# 17_FPGA_B12_B13_B14_B15.net
KiCad netlist of a schematic drawn in Altium Designer
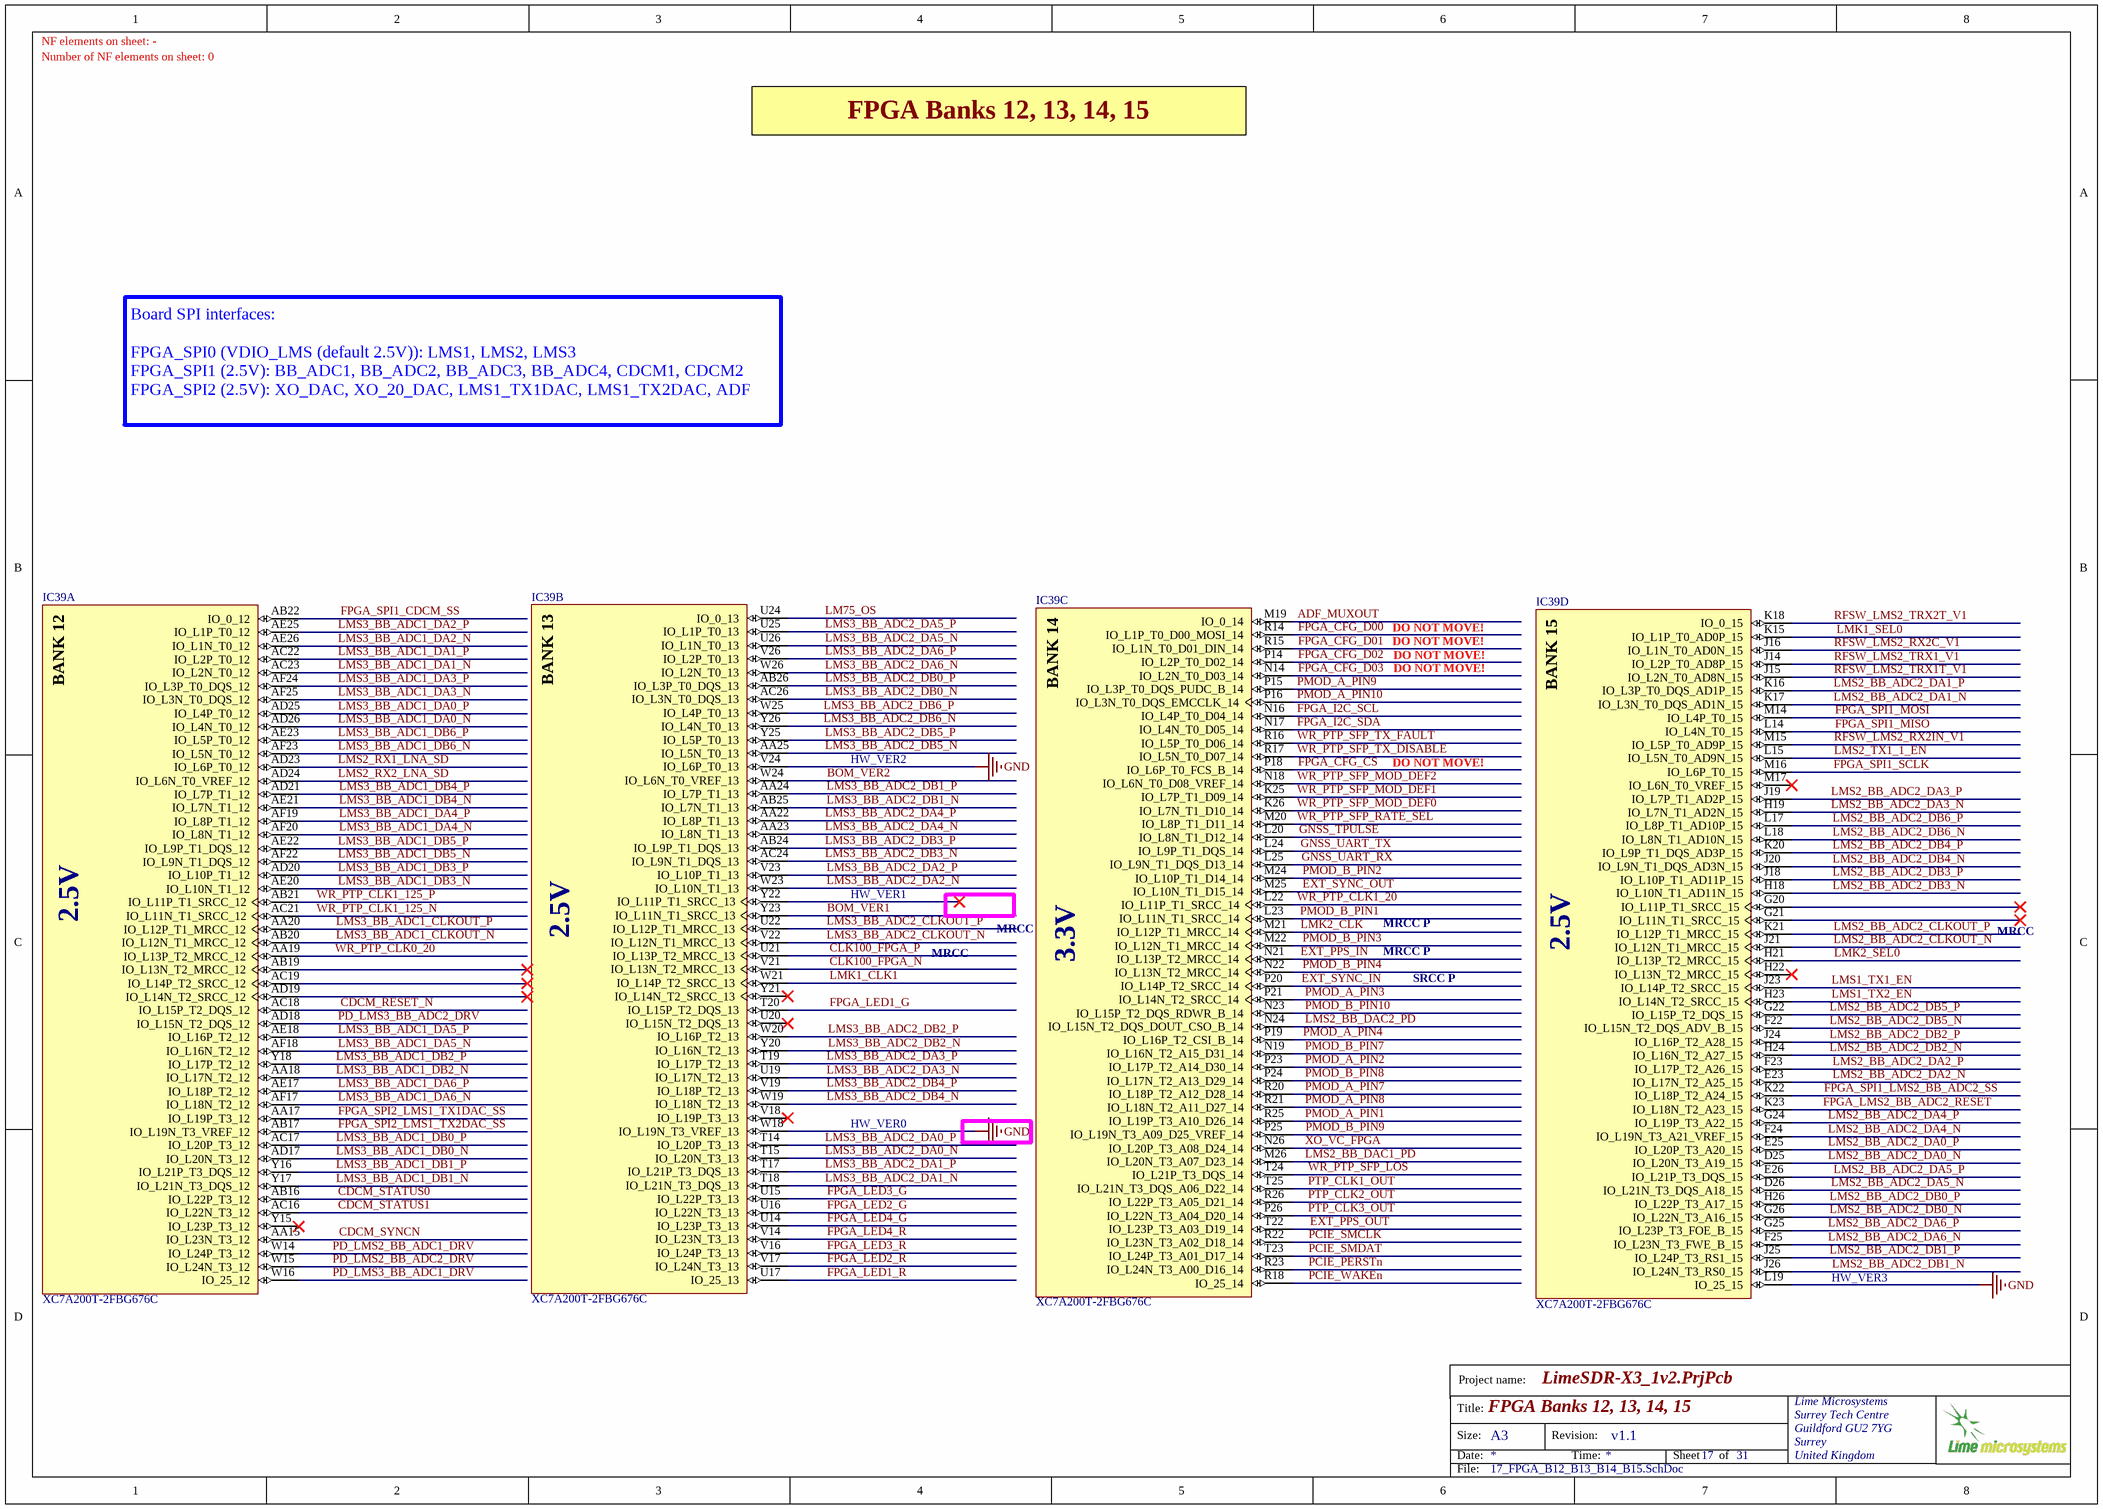
[diagram p0: 17_FPGA_B12_B13_B14_B15.SchDoc]

(export (version "E")
  (design (tool "Eeschema 10.0.6"))
  (components
    (comp (ref "IC39")
      (value "XC7A200T-2FBG676C")
      (footprint "XC7A200T-2FBG676C_FBG676")
      (description "Artix-7 FPGA, 400 User I/Os, 8 GTP, 676-Ball BGA, Speed Grade 2, Commercial Grade, Pb-Free")
      (fields (field (name "MANUFACTURER") "Xilinx"))
      (libsource (lib "LimeMicroAltiumLib_schLib_r02") (part "XC7A200T-2FBG676C"))
    )
  )
  (nets
    (net (code "1") (name "/ADF_MUXOUT") (class "Default")
      (node (ref "IC39") (pin "M19") (pinfunction "IO_0_14_M19") (pintype "bidirectional"))
    )
    (net (code "2") (name "/BOM_VER1") (class "Default")
      (node (ref "IC39") (pin "Y23") (pinfunction "IO_L11N_T1_SRCC_13_Y23") (pintype "bidirectional"))
    )
    (net (code "3") (name "/BOM_VER2") (class "Default")
      (node (ref "IC39") (pin "W24") (pinfunction "IO_L6N_T0_VREF_13_W24") (pintype "bidirectional"))
    )
    (net (code "4") (name "/CDCM_RESET_N") (class "Default")
      (node (ref "IC39") (pin "AC18") (pinfunction "IO_L15P_T2_DQS_12_AC18") (pintype "bidirectional"))
    )
    (net (code "5") (name "/CDCM_STATUS0") (class "Default")
      (node (ref "IC39") (pin "AB16") (pinfunction "IO_L22P_T3_12_AB16") (pintype "bidirectional"))
    )
    (net (code "6") (name "/CDCM_STATUS1") (class "Default")
      (node (ref "IC39") (pin "AC16") (pinfunction "IO_L22N_T3_12_AC16") (pintype "bidirectional"))
    )
    (net (code "7") (name "/CDCM_SYNCN") (class "Default")
      (node (ref "IC39") (pin "AA15") (pinfunction "IO_L23N_T3_12_AA15") (pintype "bidirectional"))
    )
    (net (code "8") (name "/CLK100_FPGA_N") (class "Default")
      (node (ref "IC39") (pin "V21") (pinfunction "IO_L13N_T2_MRCC_13_V21") (pintype "bidirectional"))
    )
    (net (code "9") (name "/CLK100_FPGA_P") (class "Default")
      (node (ref "IC39") (pin "U21") (pinfunction "IO_L13P_T2_MRCC_13_U21") (pintype "bidirectional"))
    )
    (net (code "10") (name "/EXT_PPS_IN") (class "Default")
      (node (ref "IC39") (pin "N21") (pinfunction "IO_L13P_T2_MRCC_14_N21") (pintype "bidirectional"))
    )
    (net (code "11") (name "/EXT_PPS_OUT") (class "Default")
      (node (ref "IC39") (pin "T22") (pinfunction "IO_L23P_T3_A03_D19_14_T22") (pintype "bidirectional"))
    )
    (net (code "12") (name "/EXT_SYNC_IN") (class "Default")
      (node (ref "IC39") (pin "P20") (pinfunction "IO_L14P_T2_SRCC_14_P20") (pintype "bidirectional"))
    )
    (net (code "13") (name "/EXT_SYNC_OUT") (class "Default")
      (node (ref "IC39") (pin "M25") (pinfunction "IO_L10N_T1_D15_14_M25") (pintype "bidirectional"))
    )
    (net (code "14") (name "/FPGA_CFG_CS") (class "Default")
      (node (ref "IC39") (pin "P18") (pinfunction "IO_L6P_T0_FCS_B_14_P18") (pintype "bidirectional"))
    )
    (net (code "15") (name "/FPGA_CFG_D00") (class "Default")
      (node (ref "IC39") (pin "R14") (pinfunction "IO_L1P_T0_D00_MOSI_14_R14") (pintype "bidirectional"))
    )
    (net (code "16") (name "/FPGA_CFG_D01") (class "Default")
      (node (ref "IC39") (pin "R15") (pinfunction "IO_L1N_T0_D01_DIN_14_R15") (pintype "bidirectional"))
    )
    (net (code "17") (name "/FPGA_CFG_D02") (class "Default")
      (node (ref "IC39") (pin "P14") (pinfunction "IO_L2P_T0_D02_14_P14") (pintype "bidirectional"))
    )
    (net (code "18") (name "/FPGA_CFG_D03") (class "Default")
      (node (ref "IC39") (pin "N14") (pinfunction "IO_L2N_T0_D03_14_N14") (pintype "bidirectional"))
    )
    (net (code "19") (name "/FPGA_I2C_SCL") (class "Default")
      (node (ref "IC39") (pin "N16") (pinfunction "IO_L4P_T0_D04_14_N16") (pintype "bidirectional"))
    )
    (net (code "20") (name "/FPGA_I2C_SDA") (class "Default")
      (node (ref "IC39") (pin "N17") (pinfunction "IO_L4N_T0_D05_14_N17") (pintype "bidirectional"))
    )
    (net (code "21") (name "/FPGA_LED1_G") (class "Default")
      (node (ref "IC39") (pin "T20") (pinfunction "IO_L15P_T2_DQS_13_T20") (pintype "bidirectional"))
    )
    (net (code "22") (name "/FPGA_LED1_R") (class "Default")
      (node (ref "IC39") (pin "U17") (pinfunction "IO_25_13_U17") (pintype "bidirectional"))
    )
    (net (code "23") (name "/FPGA_LED2_G") (class "Default")
      (node (ref "IC39") (pin "U16") (pinfunction "IO_L22N_T3_13_U16") (pintype "bidirectional"))
    )
    (net (code "24") (name "/FPGA_LED2_R") (class "Default")
      (node (ref "IC39") (pin "V17") (pinfunction "IO_L24N_T3_13_V17") (pintype "bidirectional"))
    )
    (net (code "25") (name "/FPGA_LED3_G") (class "Default")
      (node (ref "IC39") (pin "U15") (pinfunction "IO_L22P_T3_13_U15") (pintype "bidirectional"))
    )
    (net (code "26") (name "/FPGA_LED3_R") (class "Default")
      (node (ref "IC39") (pin "V16") (pinfunction "IO_L24P_T3_13_V16") (pintype "bidirectional"))
    )
    (net (code "27") (name "/FPGA_LED4_G") (class "Default")
      (node (ref "IC39") (pin "U14") (pinfunction "IO_L23P_T3_13_U14") (pintype "bidirectional"))
    )
    (net (code "28") (name "/FPGA_LED4_R") (class "Default")
      (node (ref "IC39") (pin "V14") (pinfunction "IO_L23N_T3_13_V14") (pintype "bidirectional"))
    )
    (net (code "29") (name "/FPGA_LMS2_BB_ADC2_RESET") (class "Default")
      (node (ref "IC39") (pin "K23") (pinfunction "IO_L18N_T2_A23_15_K23") (pintype "bidirectional"))
    )
    (net (code "30") (name "/FPGA_SPI1_CDCM_SS") (class "Default")
      (node (ref "IC39") (pin "AB22") (pinfunction "IO_0_12_AB22") (pintype "bidirectional"))
    )
    (net (code "31") (name "/FPGA_SPI1_LMS2_BB_ADC2_SS") (class "Default")
      (node (ref "IC39") (pin "K22") (pinfunction "IO_L18P_T2_A24_15_K22") (pintype "bidirectional"))
    )
    (net (code "32") (name "/FPGA_SPI1_MISO") (class "Default")
      (node (ref "IC39") (pin "L14") (pinfunction "IO_L4N_T0_15_L14") (pintype "bidirectional"))
    )
    (net (code "33") (name "/FPGA_SPI1_MOSI") (class "Default")
      (node (ref "IC39") (pin "M14") (pinfunction "IO_L4P_T0_15_M14") (pintype "bidirectional"))
    )
    (net (code "34") (name "/FPGA_SPI1_SCLK") (class "Default")
      (node (ref "IC39") (pin "M16") (pinfunction "IO_L6P_T0_15_M16") (pintype "bidirectional"))
    )
    (net (code "35") (name "/FPGA_SPI2_LMS1_TX1DAC_SS") (class "Default")
      (node (ref "IC39") (pin "AA17") (pinfunction "IO_L19P_T3_12_AA17") (pintype "bidirectional"))
    )
    (net (code "36") (name "/FPGA_SPI2_LMS1_TX2DAC_SS") (class "Default")
      (node (ref "IC39") (pin "AB17") (pinfunction "IO_L19N_T3_VREF_12_AB17") (pintype "bidirectional"))
    )
    (net (code "37") (name "/GNSS_TPULSE") (class "Default")
      (node (ref "IC39") (pin "L20") (pinfunction "IO_L8N_T1_D12_14_L20") (pintype "bidirectional"))
    )
    (net (code "38") (name "/GNSS_UART_RX") (class "Default")
      (node (ref "IC39") (pin "L25") (pinfunction "IO_L9N_T1_DQS_D13_14_L25") (pintype "bidirectional"))
    )
    (net (code "39") (name "/GNSS_UART_TX") (class "Default")
      (node (ref "IC39") (pin "L24") (pinfunction "IO_L9P_T1_DQS_14_L24") (pintype "bidirectional"))
    )
    (net (code "40") (name "/LM75_OS") (class "Default")
      (node (ref "IC39") (pin "U24") (pinfunction "IO_0_13_U24") (pintype "bidirectional"))
    )
    (net (code "41") (name "/LMK1_CLK1") (class "Default")
      (node (ref "IC39") (pin "W21") (pinfunction "IO_L14P_T2_SRCC_13_W21") (pintype "bidirectional"))
    )
    (net (code "42") (name "/LMK1_SEL0") (class "Default")
      (node (ref "IC39") (pin "K15") (pinfunction "IO_L1P_T0_AD0P_15_K15") (pintype "bidirectional"))
    )
    (net (code "43") (name "/LMK2_CLK") (class "Default")
      (node (ref "IC39") (pin "M21") (pinfunction "IO_L12P_T1_MRCC_14_M21") (pintype "bidirectional"))
    )
    (net (code "44") (name "/LMK2_SEL0") (class "Default")
      (node (ref "IC39") (pin "H21") (pinfunction "IO_L13P_T2_MRCC_15_H21") (pintype "bidirectional"))
    )
    (net (code "45") (name "/LMS1_TX1_EN") (class "Default")
      (node (ref "IC39") (pin "J23") (pinfunction "IO_L14P_T2_SRCC_15_J23") (pintype "bidirectional"))
    )
    (net (code "46") (name "/LMS1_TX2_EN") (class "Default")
      (node (ref "IC39") (pin "H23") (pinfunction "IO_L14N_T2_SRCC_15_H23") (pintype "bidirectional"))
    )
    (net (code "47") (name "/LMS2_BB_ADC2_CLKOUT_N") (class "Default")
      (node (ref "IC39") (pin "J21") (pinfunction "IO_L12N_T1_MRCC_15_J21") (pintype "bidirectional"))
    )
    (net (code "48") (name "/LMS2_BB_ADC2_CLKOUT_P") (class "Default")
      (node (ref "IC39") (pin "K21") (pinfunction "IO_L12P_T1_MRCC_15_K21") (pintype "bidirectional"))
    )
    (net (code "49") (name "/LMS2_BB_ADC2_DA0_N") (class "Default")
      (node (ref "IC39") (pin "D25") (pinfunction "IO_L20N_T3_A19_15_D25") (pintype "bidirectional"))
    )
    (net (code "50") (name "/LMS2_BB_ADC2_DA0_P") (class "Default")
      (node (ref "IC39") (pin "E25") (pinfunction "IO_L20P_T3_A20_15_E25") (pintype "bidirectional"))
    )
    (net (code "51") (name "/LMS2_BB_ADC2_DA1_N") (class "Default")
      (node (ref "IC39") (pin "K17") (pinfunction "IO_L3N_T0_DQS_AD1N_15_K17") (pintype "bidirectional"))
    )
    (net (code "52") (name "/LMS2_BB_ADC2_DA1_P") (class "Default")
      (node (ref "IC39") (pin "K16") (pinfunction "IO_L3P_T0_DQS_AD1P_15_K16") (pintype "bidirectional"))
    )
    (net (code "53") (name "/LMS2_BB_ADC2_DA2_N") (class "Default")
      (node (ref "IC39") (pin "E23") (pinfunction "IO_L17N_T2_A25_15_E23") (pintype "bidirectional"))
    )
    (net (code "54") (name "/LMS2_BB_ADC2_DA2_P") (class "Default")
      (node (ref "IC39") (pin "F23") (pinfunction "IO_L17P_T2_A26_15_F23") (pintype "bidirectional"))
    )
    (net (code "55") (name "/LMS2_BB_ADC2_DA3_N") (class "Default")
      (node (ref "IC39") (pin "H19") (pinfunction "IO_L7N_T1_AD2N_15_H19") (pintype "bidirectional"))
    )
    (net (code "56") (name "/LMS2_BB_ADC2_DA3_P") (class "Default")
      (node (ref "IC39") (pin "J19") (pinfunction "IO_L7P_T1_AD2P_15_J19") (pintype "bidirectional"))
    )
    (net (code "57") (name "/LMS2_BB_ADC2_DA4_N") (class "Default")
      (node (ref "IC39") (pin "F24") (pinfunction "IO_L19N_T3_A21_VREF_15_F24") (pintype "bidirectional"))
    )
    (net (code "58") (name "/LMS2_BB_ADC2_DA4_P") (class "Default")
      (node (ref "IC39") (pin "G24") (pinfunction "IO_L19P_T3_A22_15_G24") (pintype "bidirectional"))
    )
    (net (code "59") (name "/LMS2_BB_ADC2_DA5_N") (class "Default")
      (node (ref "IC39") (pin "D26") (pinfunction "IO_L21N_T3_DQS_A18_15_D26") (pintype "bidirectional"))
    )
    (net (code "60") (name "/LMS2_BB_ADC2_DA5_P") (class "Default")
      (node (ref "IC39") (pin "E26") (pinfunction "IO_L21P_T3_DQS_15_E26") (pintype "bidirectional"))
    )
    (net (code "61") (name "/LMS2_BB_ADC2_DA6_N") (class "Default")
      (node (ref "IC39") (pin "F25") (pinfunction "IO_L23N_T3_FWE_B_15_F25") (pintype "bidirectional"))
    )
    (net (code "62") (name "/LMS2_BB_ADC2_DA6_P") (class "Default")
      (node (ref "IC39") (pin "G25") (pinfunction "IO_L23P_T3_FOE_B_15_G25") (pintype "bidirectional"))
    )
    (net (code "63") (name "/LMS2_BB_ADC2_DB0_N") (class "Default")
      (node (ref "IC39") (pin "G26") (pinfunction "IO_L22N_T3_A16_15_G26") (pintype "bidirectional"))
    )
    (net (code "64") (name "/LMS2_BB_ADC2_DB0_P") (class "Default")
      (node (ref "IC39") (pin "H26") (pinfunction "IO_L22P_T3_A17_15_H26") (pintype "bidirectional"))
    )
    (net (code "65") (name "/LMS2_BB_ADC2_DB1_N") (class "Default")
      (node (ref "IC39") (pin "J26") (pinfunction "IO_L24N_T3_RS0_15_J26") (pintype "bidirectional"))
    )
    (net (code "66") (name "/LMS2_BB_ADC2_DB1_P") (class "Default")
      (node (ref "IC39") (pin "J25") (pinfunction "IO_L24P_T3_RS1_15_J25") (pintype "bidirectional"))
    )
    (net (code "67") (name "/LMS2_BB_ADC2_DB2_N") (class "Default")
      (node (ref "IC39") (pin "H24") (pinfunction "IO_L16N_T2_A27_15_H24") (pintype "bidirectional"))
    )
    (net (code "68") (name "/LMS2_BB_ADC2_DB2_P") (class "Default")
      (node (ref "IC39") (pin "J24") (pinfunction "IO_L16P_T2_A28_15_J24") (pintype "bidirectional"))
    )
    (net (code "69") (name "/LMS2_BB_ADC2_DB3_N") (class "Default")
      (node (ref "IC39") (pin "H18") (pinfunction "IO_L10N_T1_AD11N_15_H18") (pintype "bidirectional"))
    )
    (net (code "70") (name "/LMS2_BB_ADC2_DB3_P") (class "Default")
      (node (ref "IC39") (pin "J18") (pinfunction "IO_L10P_T1_AD11P_15_J18") (pintype "bidirectional"))
    )
    (net (code "71") (name "/LMS2_BB_ADC2_DB4_N") (class "Default")
      (node (ref "IC39") (pin "J20") (pinfunction "IO_L9N_T1_DQS_AD3N_15_J20") (pintype "bidirectional"))
    )
    (net (code "72") (name "/LMS2_BB_ADC2_DB4_P") (class "Default")
      (node (ref "IC39") (pin "K20") (pinfunction "IO_L9P_T1_DQS_AD3P_15_K20") (pintype "bidirectional"))
    )
    (net (code "73") (name "/LMS2_BB_ADC2_DB5_N") (class "Default")
      (node (ref "IC39") (pin "F22") (pinfunction "IO_L15N_T2_DQS_ADV_B_15_F22") (pintype "bidirectional"))
    )
    (net (code "74") (name "/LMS2_BB_ADC2_DB5_P") (class "Default")
      (node (ref "IC39") (pin "G22") (pinfunction "IO_L15P_T2_DQS_15_G22") (pintype "bidirectional"))
    )
    (net (code "75") (name "/LMS2_BB_ADC2_DB6_N") (class "Default")
      (node (ref "IC39") (pin "L18") (pinfunction "IO_L8N_T1_AD10N_15_L18") (pintype "bidirectional"))
    )
    (net (code "76") (name "/LMS2_BB_ADC2_DB6_P") (class "Default")
      (node (ref "IC39") (pin "L17") (pinfunction "IO_L8P_T1_AD10P_15_L17") (pintype "bidirectional"))
    )
    (net (code "77") (name "/LMS2_BB_DAC1_PD") (class "Default")
      (node (ref "IC39") (pin "M26") (pinfunction "IO_L20N_T3_A07_D23_14_M26") (pintype "bidirectional"))
    )
    (net (code "78") (name "/LMS2_BB_DAC2_PD") (class "Default")
      (node (ref "IC39") (pin "N24") (pinfunction "IO_L15N_T2_DQS_DOUT_CSO_B_14_N24") (pintype "bidirectional"))
    )
    (net (code "79") (name "/LMS2_RX1_LNA_SD") (class "Default")
      (node (ref "IC39") (pin "AD23") (pinfunction "IO_L6P_T0_12_AD23") (pintype "bidirectional"))
    )
    (net (code "80") (name "/LMS2_RX2_LNA_SD") (class "Default")
      (node (ref "IC39") (pin "AD24") (pinfunction "IO_L6N_T0_VREF_12_AD24") (pintype "bidirectional"))
    )
    (net (code "81") (name "/LMS2_TX1_1_EN") (class "Default")
      (node (ref "IC39") (pin "L15") (pinfunction "IO_L5N_T0_AD9N_15_L15") (pintype "bidirectional"))
    )
    (net (code "82") (name "/LMS3_BB_ADC1_CLKOUT_N") (class "Default")
      (node (ref "IC39") (pin "AB20") (pinfunction "IO_L12N_T1_MRCC_12_AB20") (pintype "bidirectional"))
    )
    (net (code "83") (name "/LMS3_BB_ADC1_CLKOUT_P") (class "Default")
      (node (ref "IC39") (pin "AA20") (pinfunction "IO_L12P_T1_MRCC_12_AA20") (pintype "bidirectional"))
    )
    (net (code "84") (name "/LMS3_BB_ADC1_DA0_N") (class "Default")
      (node (ref "IC39") (pin "AD26") (pinfunction "IO_L4N_T0_12_AD26") (pintype "bidirectional"))
    )
    (net (code "85") (name "/LMS3_BB_ADC1_DA0_P") (class "Default")
      (node (ref "IC39") (pin "AD25") (pinfunction "IO_L4P_T0_12_AD25") (pintype "bidirectional"))
    )
    (net (code "86") (name "/LMS3_BB_ADC1_DA1_N") (class "Default")
      (node (ref "IC39") (pin "AC23") (pinfunction "IO_L2N_T0_12_AC23") (pintype "bidirectional"))
    )
    (net (code "87") (name "/LMS3_BB_ADC1_DA1_P") (class "Default")
      (node (ref "IC39") (pin "AC22") (pinfunction "IO_L2P_T0_12_AC22") (pintype "bidirectional"))
    )
    (net (code "88") (name "/LMS3_BB_ADC1_DA2_N") (class "Default")
      (node (ref "IC39") (pin "AE26") (pinfunction "IO_L1N_T0_12_AE26") (pintype "bidirectional"))
    )
    (net (code "89") (name "/LMS3_BB_ADC1_DA2_P") (class "Default")
      (node (ref "IC39") (pin "AE25") (pinfunction "IO_L1P_T0_12_AE25") (pintype "bidirectional"))
    )
    (net (code "90") (name "/LMS3_BB_ADC1_DA3_N") (class "Default")
      (node (ref "IC39") (pin "AF25") (pinfunction "IO_L3N_T0_DQS_12_AF25") (pintype "bidirectional"))
    )
    (net (code "91") (name "/LMS3_BB_ADC1_DA3_P") (class "Default")
      (node (ref "IC39") (pin "AF24") (pinfunction "IO_L3P_T0_DQS_12_AF24") (pintype "bidirectional"))
    )
    (net (code "92") (name "/LMS3_BB_ADC1_DA4_N") (class "Default")
      (node (ref "IC39") (pin "AF20") (pinfunction "IO_L8N_T1_12_AF20") (pintype "bidirectional"))
    )
    (net (code "93") (name "/LMS3_BB_ADC1_DA4_P") (class "Default")
      (node (ref "IC39") (pin "AF19") (pinfunction "IO_L8P_T1_12_AF19") (pintype "bidirectional"))
    )
    (net (code "94") (name "/LMS3_BB_ADC1_DA5_N") (class "Default")
      (node (ref "IC39") (pin "AF18") (pinfunction "IO_L16N_T2_12_AF18") (pintype "bidirectional"))
    )
    (net (code "95") (name "/LMS3_BB_ADC1_DA5_P") (class "Default")
      (node (ref "IC39") (pin "AE18") (pinfunction "IO_L16P_T2_12_AE18") (pintype "bidirectional"))
    )
    (net (code "96") (name "/LMS3_BB_ADC1_DA6_N") (class "Default")
      (node (ref "IC39") (pin "AF17") (pinfunction "IO_L18N_T2_12_AF17") (pintype "bidirectional"))
    )
    (net (code "97") (name "/LMS3_BB_ADC1_DA6_P") (class "Default")
      (node (ref "IC39") (pin "AE17") (pinfunction "IO_L18P_T2_12_AE17") (pintype "bidirectional"))
    )
    (net (code "98") (name "/LMS3_BB_ADC1_DB0_N") (class "Default")
      (node (ref "IC39") (pin "AD17") (pinfunction "IO_L20N_T3_12_AD17") (pintype "bidirectional"))
    )
    (net (code "99") (name "/LMS3_BB_ADC1_DB0_P") (class "Default")
      (node (ref "IC39") (pin "AC17") (pinfunction "IO_L20P_T3_12_AC17") (pintype "bidirectional"))
    )
    (net (code "100") (name "/LMS3_BB_ADC1_DB1_N") (class "Default")
      (node (ref "IC39") (pin "Y17") (pinfunction "IO_L21N_T3_DQS_12_Y17") (pintype "bidirectional"))
    )
    (net (code "101") (name "/LMS3_BB_ADC1_DB1_P") (class "Default")
      (node (ref "IC39") (pin "Y16") (pinfunction "IO_L21P_T3_DQS_12_Y16") (pintype "bidirectional"))
    )
    (net (code "102") (name "/LMS3_BB_ADC1_DB2_N") (class "Default")
      (node (ref "IC39") (pin "AA18") (pinfunction "IO_L17N_T2_12_AA18") (pintype "bidirectional"))
    )
    (net (code "103") (name "/LMS3_BB_ADC1_DB2_P") (class "Default")
      (node (ref "IC39") (pin "Y18") (pinfunction "IO_L17P_T2_12_Y18") (pintype "bidirectional"))
    )
    (net (code "104") (name "/LMS3_BB_ADC1_DB3_N") (class "Default")
      (node (ref "IC39") (pin "AE20") (pinfunction "IO_L10N_T1_12_AE20") (pintype "bidirectional"))
    )
    (net (code "105") (name "/LMS3_BB_ADC1_DB3_P") (class "Default")
      (node (ref "IC39") (pin "AD20") (pinfunction "IO_L10P_T1_12_AD20") (pintype "bidirectional"))
    )
    (net (code "106") (name "/LMS3_BB_ADC1_DB4_N") (class "Default")
      (node (ref "IC39") (pin "AE21") (pinfunction "IO_L7N_T1_12_AE21") (pintype "bidirectional"))
    )
    (net (code "107") (name "/LMS3_BB_ADC1_DB4_P") (class "Default")
      (node (ref "IC39") (pin "AD21") (pinfunction "IO_L7P_T1_12_AD21") (pintype "bidirectional"))
    )
    (net (code "108") (name "/LMS3_BB_ADC1_DB5_N") (class "Default")
      (node (ref "IC39") (pin "AF22") (pinfunction "IO_L9N_T1_DQS_12_AF22") (pintype "bidirectional"))
    )
    (net (code "109") (name "/LMS3_BB_ADC1_DB5_P") (class "Default")
      (node (ref "IC39") (pin "AE22") (pinfunction "IO_L9P_T1_DQS_12_AE22") (pintype "bidirectional"))
    )
    (net (code "110") (name "/LMS3_BB_ADC1_DB6_N") (class "Default")
      (node (ref "IC39") (pin "AF23") (pinfunction "IO_L5N_T0_12_AF23") (pintype "bidirectional"))
    )
    (net (code "111") (name "/LMS3_BB_ADC1_DB6_P") (class "Default")
      (node (ref "IC39") (pin "AE23") (pinfunction "IO_L5P_T0_12_AE23") (pintype "bidirectional"))
    )
    (net (code "112") (name "/LMS3_BB_ADC2_CLKOUT_N") (class "Default")
      (node (ref "IC39") (pin "V22") (pinfunction "IO_L12N_T1_MRCC_13_V22") (pintype "bidirectional"))
    )
    (net (code "113") (name "/LMS3_BB_ADC2_CLKOUT_P") (class "Default")
      (node (ref "IC39") (pin "U22") (pinfunction "IO_L12P_T1_MRCC_13_U22") (pintype "bidirectional"))
    )
    (net (code "114") (name "/LMS3_BB_ADC2_DA0_N") (class "Default")
      (node (ref "IC39") (pin "T15") (pinfunction "IO_L20N_T3_13_T15") (pintype "bidirectional"))
    )
    (net (code "115") (name "/LMS3_BB_ADC2_DA0_P") (class "Default")
      (node (ref "IC39") (pin "T14") (pinfunction "IO_L20P_T3_13_T14") (pintype "bidirectional"))
    )
    (net (code "116") (name "/LMS3_BB_ADC2_DA1_N") (class "Default")
      (node (ref "IC39") (pin "T18") (pinfunction "IO_L21N_T3_DQS_13_T18") (pintype "bidirectional"))
    )
    (net (code "117") (name "/LMS3_BB_ADC2_DA1_P") (class "Default")
      (node (ref "IC39") (pin "T17") (pinfunction "IO_L21P_T3_DQS_13_T17") (pintype "bidirectional"))
    )
    (net (code "118") (name "/LMS3_BB_ADC2_DA2_N") (class "Default")
      (node (ref "IC39") (pin "W23") (pinfunction "IO_L10N_T1_13_W23") (pintype "bidirectional"))
    )
    (net (code "119") (name "/LMS3_BB_ADC2_DA2_P") (class "Default")
      (node (ref "IC39") (pin "V23") (pinfunction "IO_L10P_T1_13_V23") (pintype "bidirectional"))
    )
    (net (code "120") (name "/LMS3_BB_ADC2_DA3_N") (class "Default")
      (node (ref "IC39") (pin "U19") (pinfunction "IO_L17N_T2_13_U19") (pintype "bidirectional"))
    )
    (net (code "121") (name "/LMS3_BB_ADC2_DA3_P") (class "Default")
      (node (ref "IC39") (pin "T19") (pinfunction "IO_L17P_T2_13_T19") (pintype "bidirectional"))
    )
    (net (code "122") (name "/LMS3_BB_ADC2_DA4_N") (class "Default")
      (node (ref "IC39") (pin "AA23") (pinfunction "IO_L8N_T1_13_AA23") (pintype "bidirectional"))
    )
    (net (code "123") (name "/LMS3_BB_ADC2_DA4_P") (class "Default")
      (node (ref "IC39") (pin "AA22") (pinfunction "IO_L8P_T1_13_AA22") (pintype "bidirectional"))
    )
    (net (code "124") (name "/LMS3_BB_ADC2_DA5_N") (class "Default")
      (node (ref "IC39") (pin "U26") (pinfunction "IO_L1N_T0_13_U26") (pintype "bidirectional"))
    )
    (net (code "125") (name "/LMS3_BB_ADC2_DA5_P") (class "Default")
      (node (ref "IC39") (pin "U25") (pinfunction "IO_L1P_T0_13_U25") (pintype "bidirectional"))
    )
    (net (code "126") (name "/LMS3_BB_ADC2_DA6_N") (class "Default")
      (node (ref "IC39") (pin "W26") (pinfunction "IO_L2N_T0_13_W26") (pintype "bidirectional"))
    )
    (net (code "127") (name "/LMS3_BB_ADC2_DA6_P") (class "Default")
      (node (ref "IC39") (pin "V26") (pinfunction "IO_L2P_T0_13_V26") (pintype "bidirectional"))
    )
    (net (code "128") (name "/LMS3_BB_ADC2_DB0_N") (class "Default")
      (node (ref "IC39") (pin "AC26") (pinfunction "IO_L3N_T0_DQS_13_AC26") (pintype "bidirectional"))
    )
    (net (code "129") (name "/LMS3_BB_ADC2_DB0_P") (class "Default")
      (node (ref "IC39") (pin "AB26") (pinfunction "IO_L3P_T0_DQS_13_AB26") (pintype "bidirectional"))
    )
    (net (code "130") (name "/LMS3_BB_ADC2_DB1_N") (class "Default")
      (node (ref "IC39") (pin "AB25") (pinfunction "IO_L7N_T1_13_AB25") (pintype "bidirectional"))
    )
    (net (code "131") (name "/LMS3_BB_ADC2_DB1_P") (class "Default")
      (node (ref "IC39") (pin "AA24") (pinfunction "IO_L7P_T1_13_AA24") (pintype "bidirectional"))
    )
    (net (code "132") (name "/LMS3_BB_ADC2_DB2_N") (class "Default")
      (node (ref "IC39") (pin "Y20") (pinfunction "IO_L16N_T2_13_Y20") (pintype "bidirectional"))
    )
    (net (code "133") (name "/LMS3_BB_ADC2_DB2_P") (class "Default")
      (node (ref "IC39") (pin "W20") (pinfunction "IO_L16P_T2_13_W20") (pintype "bidirectional"))
    )
    (net (code "134") (name "/LMS3_BB_ADC2_DB3_N") (class "Default")
      (node (ref "IC39") (pin "AC24") (pinfunction "IO_L9N_T1_DQS_13_AC24") (pintype "bidirectional"))
    )
    (net (code "135") (name "/LMS3_BB_ADC2_DB3_P") (class "Default")
      (node (ref "IC39") (pin "AB24") (pinfunction "IO_L9P_T1_DQS_13_AB24") (pintype "bidirectional"))
    )
    (net (code "136") (name "/LMS3_BB_ADC2_DB4_N") (class "Default")
      (node (ref "IC39") (pin "W19") (pinfunction "IO_L18N_T2_13_W19") (pintype "bidirectional"))
    )
    (net (code "137") (name "/LMS3_BB_ADC2_DB4_P") (class "Default")
      (node (ref "IC39") (pin "V19") (pinfunction "IO_L18P_T2_13_V19") (pintype "bidirectional"))
    )
    (net (code "138") (name "/LMS3_BB_ADC2_DB5_N") (class "Default")
      (node (ref "IC39") (pin "AA25") (pinfunction "IO_L5N_T0_13_AA25") (pintype "bidirectional"))
    )
    (net (code "139") (name "/LMS3_BB_ADC2_DB5_P") (class "Default")
      (node (ref "IC39") (pin "Y25") (pinfunction "IO_L5P_T0_13_Y25") (pintype "bidirectional"))
    )
    (net (code "140") (name "/LMS3_BB_ADC2_DB6_N") (class "Default")
      (node (ref "IC39") (pin "Y26") (pinfunction "IO_L4N_T0_13_Y26") (pintype "bidirectional"))
    )
    (net (code "141") (name "/LMS3_BB_ADC2_DB6_P") (class "Default")
      (node (ref "IC39") (pin "W25") (pinfunction "IO_L4P_T0_13_W25") (pintype "bidirectional"))
    )
    (net (code "142") (name "/PCIE_PERSTn") (class "Default")
      (node (ref "IC39") (pin "R23") (pinfunction "IO_L24N_T3_A00_D16_14_R23") (pintype "bidirectional"))
    )
    (net (code "143") (name "/PCIE_SMCLK") (class "Default")
      (node (ref "IC39") (pin "R22") (pinfunction "IO_L23N_T3_A02_D18_14_R22") (pintype "bidirectional"))
    )
    (net (code "144") (name "/PCIE_SMDAT") (class "Default")
      (node (ref "IC39") (pin "T23") (pinfunction "IO_L24P_T3_A01_D17_14_T23") (pintype "bidirectional"))
    )
    (net (code "145") (name "/PCIE_WAKEn") (class "Default")
      (node (ref "IC39") (pin "R18") (pinfunction "IO_25_14_R18") (pintype "bidirectional"))
    )
    (net (code "146") (name "/PD_LMS2_BB_ADC1_DRV") (class "Default")
      (node (ref "IC39") (pin "W14") (pinfunction "IO_L24P_T3_12_W14") (pintype "bidirectional"))
    )
    (net (code "147") (name "/PD_LMS2_BB_ADC2_DRV") (class "Default")
      (node (ref "IC39") (pin "W15") (pinfunction "IO_L24N_T3_12_W15") (pintype "bidirectional"))
    )
    (net (code "148") (name "/PD_LMS3_BB_ADC1_DRV") (class "Default")
      (node (ref "IC39") (pin "W16") (pinfunction "IO_25_12_W16") (pintype "bidirectional"))
    )
    (net (code "149") (name "/PD_LMS3_BB_ADC2_DRV") (class "Default")
      (node (ref "IC39") (pin "AD18") (pinfunction "IO_L15N_T2_DQS_12_AD18") (pintype "bidirectional"))
    )
    (net (code "150") (name "/PMOD_A_PIN1") (class "Default")
      (node (ref "IC39") (pin "R25") (pinfunction "IO_L19P_T3_A10_D26_14_R25") (pintype "bidirectional"))
    )
    (net (code "151") (name "/PMOD_A_PIN2") (class "Default")
      (node (ref "IC39") (pin "P23") (pinfunction "IO_L17P_T2_A14_D30_14_P23") (pintype "bidirectional"))
    )
    (net (code "152") (name "/PMOD_A_PIN3") (class "Default")
      (node (ref "IC39") (pin "P21") (pinfunction "IO_L14N_T2_SRCC_14_P21") (pintype "bidirectional"))
    )
    (net (code "153") (name "/PMOD_A_PIN4") (class "Default")
      (node (ref "IC39") (pin "P19") (pinfunction "IO_L16P_T2_CSI_B_14_P19") (pintype "bidirectional"))
    )
    (net (code "154") (name "/PMOD_A_PIN7") (class "Default")
      (node (ref "IC39") (pin "R20") (pinfunction "IO_L18P_T2_A12_D28_14_R20") (pintype "bidirectional"))
    )
    (net (code "155") (name "/PMOD_A_PIN8") (class "Default")
      (node (ref "IC39") (pin "R21") (pinfunction "IO_L18N_T2_A11_D27_14_R21") (pintype "bidirectional"))
    )
    (net (code "156") (name "/PMOD_A_PIN9") (class "Default")
      (node (ref "IC39") (pin "P15") (pinfunction "IO_L3P_T0_DQS_PUDC_B_14_P15") (pintype "bidirectional"))
    )
    (net (code "157") (name "/PMOD_A_PIN10") (class "Default")
      (node (ref "IC39") (pin "P16") (pinfunction "IO_L3N_T0_DQS_EMCCLK_14_P16") (pintype "bidirectional"))
    )
    (net (code "158") (name "/PMOD_B_PIN1") (class "Default")
      (node (ref "IC39") (pin "L23") (pinfunction "IO_L11N_T1_SRCC_14_L23") (pintype "bidirectional"))
    )
    (net (code "159") (name "/PMOD_B_PIN2") (class "Default")
      (node (ref "IC39") (pin "M24") (pinfunction "IO_L10P_T1_D14_14_M24") (pintype "bidirectional"))
    )
    (net (code "160") (name "/PMOD_B_PIN3") (class "Default")
      (node (ref "IC39") (pin "M22") (pinfunction "IO_L12N_T1_MRCC_14_M22") (pintype "bidirectional"))
    )
    (net (code "161") (name "/PMOD_B_PIN4") (class "Default")
      (node (ref "IC39") (pin "N22") (pinfunction "IO_L13N_T2_MRCC_14_N22") (pintype "bidirectional"))
    )
    (net (code "162") (name "/PMOD_B_PIN7") (class "Default")
      (node (ref "IC39") (pin "N19") (pinfunction "IO_L16N_T2_A15_D31_14_N19") (pintype "bidirectional"))
    )
    (net (code "163") (name "/PMOD_B_PIN8") (class "Default")
      (node (ref "IC39") (pin "P24") (pinfunction "IO_L17N_T2_A13_D29_14_P24") (pintype "bidirectional"))
    )
    (net (code "164") (name "/PMOD_B_PIN9") (class "Default")
      (node (ref "IC39") (pin "P25") (pinfunction "IO_L19N_T3_A09_D25_VREF_14_P25") (pintype "bidirectional"))
    )
    (net (code "165") (name "/PMOD_B_PIN10") (class "Default")
      (node (ref "IC39") (pin "N23") (pinfunction "IO_L15P_T2_DQS_RDWR_B_14_N23") (pintype "bidirectional"))
    )
    (net (code "166") (name "/PTP_CLK1_OUT") (class "Default")
      (node (ref "IC39") (pin "T25") (pinfunction "IO_L21N_T3_DQS_A06_D22_14_T25") (pintype "bidirectional"))
    )
    (net (code "167") (name "/PTP_CLK2_OUT") (class "Default")
      (node (ref "IC39") (pin "R26") (pinfunction "IO_L22P_T3_A05_D21_14_R26") (pintype "bidirectional"))
    )
    (net (code "168") (name "/PTP_CLK3_OUT") (class "Default")
      (node (ref "IC39") (pin "P26") (pinfunction "IO_L22N_T3_A04_D20_14_P26") (pintype "bidirectional"))
    )
    (net (code "169") (name "/RFSW_LMS2_RX2C_V1") (class "Default")
      (node (ref "IC39") (pin "J16") (pinfunction "IO_L1N_T0_AD0N_15_J16") (pintype "bidirectional"))
    )
    (net (code "170") (name "/RFSW_LMS2_RX2IN_V1") (class "Default")
      (node (ref "IC39") (pin "M15") (pinfunction "IO_L5P_T0_AD9P_15_M15") (pintype "bidirectional"))
    )
    (net (code "171") (name "/RFSW_LMS2_TRX1T_V1") (class "Default")
      (node (ref "IC39") (pin "J15") (pinfunction "IO_L2N_T0_AD8N_15_J15") (pintype "bidirectional"))
    )
    (net (code "172") (name "/RFSW_LMS2_TRX1_V1") (class "Default")
      (node (ref "IC39") (pin "J14") (pinfunction "IO_L2P_T0_AD8P_15_J14") (pintype "bidirectional"))
    )
    (net (code "173") (name "/RFSW_LMS2_TRX2T_V1") (class "Default")
      (node (ref "IC39") (pin "K18") (pinfunction "IO_0_15_K18") (pintype "bidirectional"))
    )
    (net (code "174") (name "/WR_PTP_CLK0_20") (class "Default")
      (node (ref "IC39") (pin "AA19") (pinfunction "IO_L13P_T2_MRCC_12_AA19") (pintype "bidirectional"))
    )
    (net (code "175") (name "/WR_PTP_CLK1_20") (class "Default")
      (node (ref "IC39") (pin "L22") (pinfunction "IO_L11P_T1_SRCC_14_L22") (pintype "bidirectional"))
    )
    (net (code "176") (name "/WR_PTP_CLK1_125_N") (class "Default")
      (node (ref "IC39") (pin "AC21") (pinfunction "IO_L11N_T1_SRCC_12_AC21") (pintype "bidirectional"))
    )
    (net (code "177") (name "/WR_PTP_CLK1_125_P") (class "Default")
      (node (ref "IC39") (pin "AB21") (pinfunction "IO_L11P_T1_SRCC_12_AB21") (pintype "bidirectional"))
    )
    (net (code "178") (name "/WR_PTP_SFP_LOS") (class "Default")
      (node (ref "IC39") (pin "T24") (pinfunction "IO_L21P_T3_DQS_14_T24") (pintype "bidirectional"))
    )
    (net (code "179") (name "/WR_PTP_SFP_MOD_DEF0") (class "Default")
      (node (ref "IC39") (pin "K26") (pinfunction "IO_L7N_T1_D10_14_K26") (pintype "bidirectional"))
    )
    (net (code "180") (name "/WR_PTP_SFP_MOD_DEF1") (class "Default")
      (node (ref "IC39") (pin "K25") (pinfunction "IO_L7P_T1_D09_14_K25") (pintype "bidirectional"))
    )
    (net (code "181") (name "/WR_PTP_SFP_MOD_DEF2") (class "Default")
      (node (ref "IC39") (pin "N18") (pinfunction "IO_L6N_T0_D08_VREF_14_N18") (pintype "bidirectional"))
    )
    (net (code "182") (name "/WR_PTP_SFP_RATE_SEL") (class "Default")
      (node (ref "IC39") (pin "M20") (pinfunction "IO_L8P_T1_D11_14_M20") (pintype "bidirectional"))
    )
    (net (code "183") (name "/WR_PTP_SFP_TX_DISABLE") (class "Default")
      (node (ref "IC39") (pin "R17") (pinfunction "IO_L5N_T0_D07_14_R17") (pintype "bidirectional"))
    )
    (net (code "184") (name "/WR_PTP_SFP_TX_FAULT") (class "Default")
      (node (ref "IC39") (pin "R16") (pinfunction "IO_L5P_T0_D06_14_R16") (pintype "bidirectional"))
    )
    (net (code "185") (name "/XO_VC_FPGA") (class "Default")
      (node (ref "IC39") (pin "N26") (pinfunction "IO_L20P_T3_A08_D24_14_N26") (pintype "bidirectional"))
    )
    (net (code "186") (name "GND") (class "Default")
      (node (ref "IC39") (pin "L19") (pinfunction "IO_25_15_L19") (pintype "bidirectional"))
      (node (ref "IC39") (pin "V24") (pinfunction "IO_L6P_T0_13_V24") (pintype "bidirectional"))
      (node (ref "IC39") (pin "W18") (pinfunction "IO_L19N_T3_VREF_13_W18") (pintype "bidirectional"))
    )
    (net (code "187") (name "unconnected-(IC39A-IO_L13N_T2_MRCC_12-PadAB19)") (class "Default")
      (node (ref "IC39") (pin "AB19") (pinfunction "IO_L13N_T2_MRCC_12_AB19") (pintype "bidirectional+no_connect"))
    )
    (net (code "188") (name "unconnected-(IC39A-IO_L14N_T2_SRCC_12-PadAD19)") (class "Default")
      (node (ref "IC39") (pin "AD19") (pinfunction "IO_L14N_T2_SRCC_12_AD19") (pintype "bidirectional+no_connect"))
    )
    (net (code "189") (name "unconnected-(IC39A-IO_L14P_T2_SRCC_12-PadAC19)") (class "Default")
      (node (ref "IC39") (pin "AC19") (pinfunction "IO_L14P_T2_SRCC_12_AC19") (pintype "bidirectional+no_connect"))
    )
    (net (code "190") (name "unconnected-(IC39A-IO_L23P_T3_12-PadY15)") (class "Default")
      (node (ref "IC39") (pin "Y15") (pinfunction "IO_L23P_T3_12_Y15") (pintype "bidirectional+no_connect"))
    )
    (net (code "191") (name "unconnected-(IC39B-IO_L11P_T1_SRCC_13-PadY22)") (class "Default")
      (node (ref "IC39") (pin "Y22") (pinfunction "IO_L11P_T1_SRCC_13_Y22") (pintype "bidirectional+no_connect"))
    )
    (net (code "192") (name "unconnected-(IC39B-IO_L14N_T2_SRCC_13-PadY21)") (class "Default")
      (node (ref "IC39") (pin "Y21") (pinfunction "IO_L14N_T2_SRCC_13_Y21") (pintype "bidirectional+no_connect"))
    )
    (net (code "193") (name "unconnected-(IC39B-IO_L15N_T2_DQS_13-PadU20)") (class "Default")
      (node (ref "IC39") (pin "U20") (pinfunction "IO_L15N_T2_DQS_13_U20") (pintype "bidirectional+no_connect"))
    )
    (net (code "194") (name "unconnected-(IC39B-IO_L19P_T3_13-PadV18)") (class "Default")
      (node (ref "IC39") (pin "V18") (pinfunction "IO_L19P_T3_13_V18") (pintype "bidirectional+no_connect"))
    )
    (net (code "195") (name "unconnected-(IC39D-IO_L6N_T0_VREF_15-PadM17)") (class "Default")
      (node (ref "IC39") (pin "M17") (pinfunction "IO_L6N_T0_VREF_15_M17") (pintype "bidirectional+no_connect"))
    )
    (net (code "196") (name "unconnected-(IC39D-IO_L11N_T1_SRCC_15-PadG21)") (class "Default")
      (node (ref "IC39") (pin "G21") (pinfunction "IO_L11N_T1_SRCC_15_G21") (pintype "bidirectional+no_connect"))
    )
    (net (code "197") (name "unconnected-(IC39D-IO_L11P_T1_SRCC_15-PadG20)") (class "Default")
      (node (ref "IC39") (pin "G20") (pinfunction "IO_L11P_T1_SRCC_15_G20") (pintype "bidirectional+no_connect"))
    )
    (net (code "198") (name "unconnected-(IC39D-IO_L13N_T2_MRCC_15-PadH22)") (class "Default")
      (node (ref "IC39") (pin "H22") (pinfunction "IO_L13N_T2_MRCC_15_H22") (pintype "bidirectional+no_connect"))
    )
  )
)
